# rpi2_ctrl.net
KiCad netlist of a schematic drawn in EAGLE
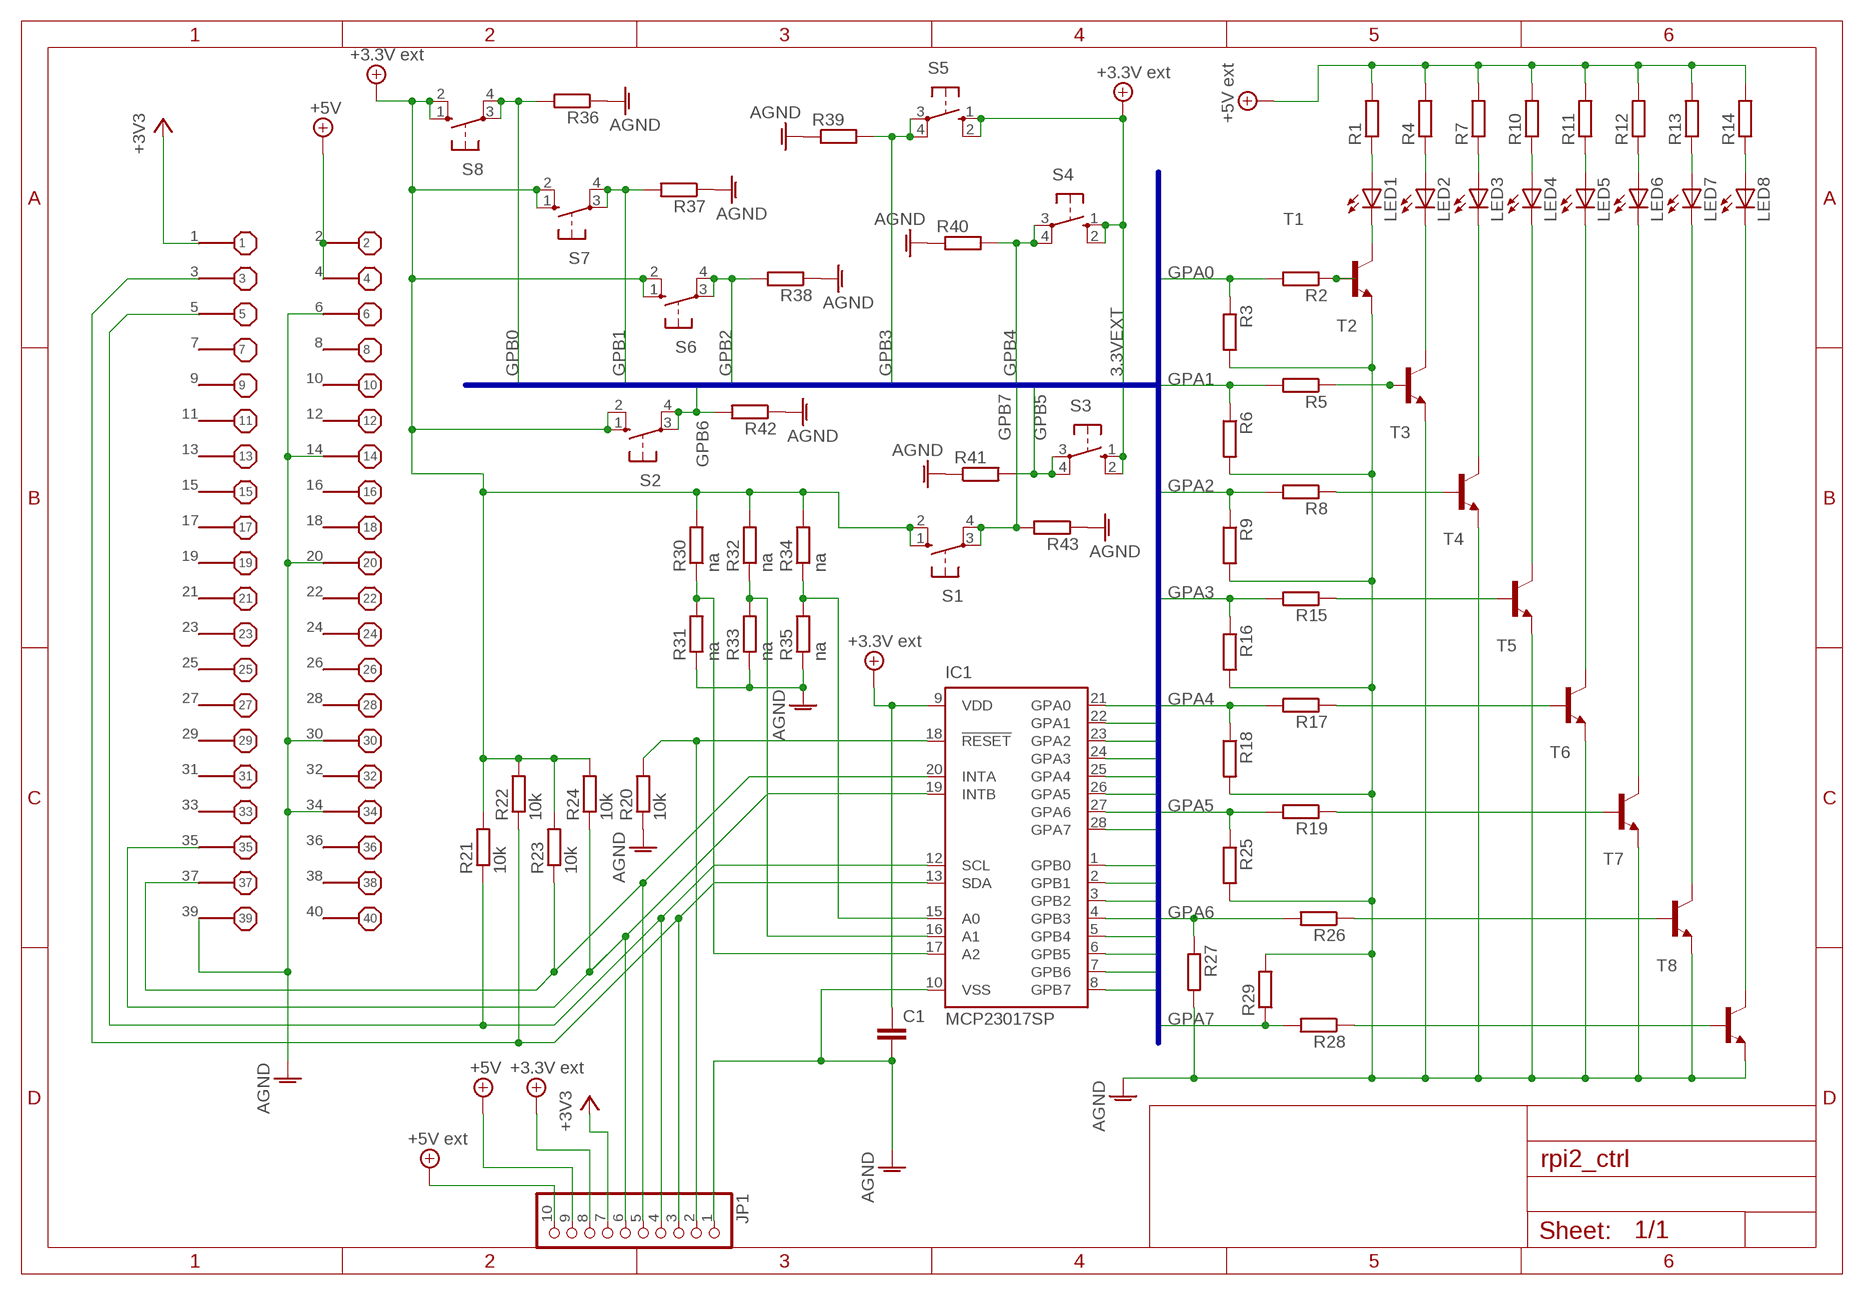
[diagram p0: schematic, sheet 1]

(export (version "E")
  (design (tool "Eeschema 10.0.6"))
  (components
    (comp (ref "C1")
      (value "C-EUC1210")
      (footprint "eagle-import:C1210")
      (libsource (lib "eagle-import") (part "C-EUC1210"))
    )
    (comp (ref "IC1")
      (value "MCP23017SP")
      (footprint "eagle-import:DIL28-3")
      (fields (field (name "MF") "MICROCHIP") (field (name "MPN") "MCP23017-E/SP"))
      (libsource (lib "eagle-import") (part "MCP23017SP"))
    )
    (comp (ref "JP1")
      (value "PINHD-1X10")
      (footprint "eagle-import:1X10")
      (libsource (lib "eagle-import") (part "PINHD-1X10"))
    )
    (comp (ref "LED1")
      (value "LED5MM")
      (footprint "eagle-import:LED5MM")
      (libsource (lib "eagle-import") (part "LED5MM"))
    )
    (comp (ref "LED2")
      (value "LED5MM")
      (footprint "eagle-import:LED5MM")
      (libsource (lib "eagle-import") (part "LED5MM"))
    )
    (comp (ref "LED3")
      (value "LED5MM")
      (footprint "eagle-import:LED5MM")
      (libsource (lib "eagle-import") (part "LED5MM"))
    )
    (comp (ref "LED4")
      (value "LED5MM")
      (footprint "eagle-import:LED5MM")
      (libsource (lib "eagle-import") (part "LED5MM"))
    )
    (comp (ref "LED5")
      (value "LED5MM")
      (footprint "eagle-import:LED5MM")
      (libsource (lib "eagle-import") (part "LED5MM"))
    )
    (comp (ref "LED6")
      (value "LED5MM")
      (footprint "eagle-import:LED5MM")
      (libsource (lib "eagle-import") (part "LED5MM"))
    )
    (comp (ref "LED7")
      (value "LED5MM")
      (footprint "eagle-import:LED5MM")
      (libsource (lib "eagle-import") (part "LED5MM"))
    )
    (comp (ref "LED8")
      (value "LED5MM")
      (footprint "eagle-import:LED5MM")
      (libsource (lib "eagle-import") (part "LED5MM"))
    )
    (comp (ref "R1")
      (value "R-EU_R0805")
      (footprint "eagle-import:R0805")
      (libsource (lib "eagle-import") (part "R-EU_R0805"))
    )
    (comp (ref "R2")
      (value "R-EU_R0805")
      (footprint "eagle-import:R0805")
      (libsource (lib "eagle-import") (part "R-EU_R0805"))
    )
    (comp (ref "R3")
      (value "R-EU_R0805")
      (footprint "eagle-import:R0805")
      (libsource (lib "eagle-import") (part "R-EU_R0805"))
    )
    (comp (ref "R4")
      (value "R-EU_R0805")
      (footprint "eagle-import:R0805")
      (libsource (lib "eagle-import") (part "R-EU_R0805"))
    )
    (comp (ref "R5")
      (value "R-EU_R0805")
      (footprint "eagle-import:R0805")
      (libsource (lib "eagle-import") (part "R-EU_R0805"))
    )
    (comp (ref "R6")
      (value "R-EU_R0805")
      (footprint "eagle-import:R0805")
      (libsource (lib "eagle-import") (part "R-EU_R0805"))
    )
    (comp (ref "R7")
      (value "R-EU_R0805")
      (footprint "eagle-import:R0805")
      (libsource (lib "eagle-import") (part "R-EU_R0805"))
    )
    (comp (ref "R8")
      (value "R-EU_R0805")
      (footprint "eagle-import:R0805")
      (libsource (lib "eagle-import") (part "R-EU_R0805"))
    )
    (comp (ref "R9")
      (value "R-EU_R0805")
      (footprint "eagle-import:R0805")
      (libsource (lib "eagle-import") (part "R-EU_R0805"))
    )
    (comp (ref "R10")
      (value "R-EU_R0805")
      (footprint "eagle-import:R0805")
      (libsource (lib "eagle-import") (part "R-EU_R0805"))
    )
    (comp (ref "R11")
      (value "R-EU_R0805")
      (footprint "eagle-import:R0805")
      (libsource (lib "eagle-import") (part "R-EU_R0805"))
    )
    (comp (ref "R12")
      (value "R-EU_R0805")
      (footprint "eagle-import:R0805")
      (libsource (lib "eagle-import") (part "R-EU_R0805"))
    )
    (comp (ref "R13")
      (value "R-EU_R0805")
      (footprint "eagle-import:R0805")
      (libsource (lib "eagle-import") (part "R-EU_R0805"))
    )
    (comp (ref "R14")
      (value "R-EU_R0805")
      (footprint "eagle-import:R0805")
      (libsource (lib "eagle-import") (part "R-EU_R0805"))
    )
    (comp (ref "R15")
      (value "R-EU_R0805")
      (footprint "eagle-import:R0805")
      (libsource (lib "eagle-import") (part "R-EU_R0805"))
    )
    (comp (ref "R16")
      (value "R-EU_R0805")
      (footprint "eagle-import:R0805")
      (libsource (lib "eagle-import") (part "R-EU_R0805"))
    )
    (comp (ref "R17")
      (value "R-EU_R0805")
      (footprint "eagle-import:R0805")
      (libsource (lib "eagle-import") (part "R-EU_R0805"))
    )
    (comp (ref "R18")
      (value "R-EU_R0805")
      (footprint "eagle-import:R0805")
      (libsource (lib "eagle-import") (part "R-EU_R0805"))
    )
    (comp (ref "R19")
      (value "R-EU_R0805")
      (footprint "eagle-import:R0805")
      (libsource (lib "eagle-import") (part "R-EU_R0805"))
    )
    (comp (ref "R20")
      (value "10k")
      (footprint "eagle-import:R0805")
      (libsource (lib "eagle-import") (part "R-EU_R0805"))
    )
    (comp (ref "R21")
      (value "10k")
      (footprint "eagle-import:R0805")
      (libsource (lib "eagle-import") (part "R-EU_R0805"))
    )
    (comp (ref "R22")
      (value "10k")
      (footprint "eagle-import:R0805")
      (libsource (lib "eagle-import") (part "R-EU_R0805"))
    )
    (comp (ref "R23")
      (value "10k")
      (footprint "eagle-import:R0805")
      (libsource (lib "eagle-import") (part "R-EU_R0805"))
    )
    (comp (ref "R24")
      (value "10k")
      (footprint "eagle-import:R0805")
      (libsource (lib "eagle-import") (part "R-EU_R0805"))
    )
    (comp (ref "R25")
      (value "R-EU_R0805")
      (footprint "eagle-import:R0805")
      (libsource (lib "eagle-import") (part "R-EU_R0805"))
    )
    (comp (ref "R26")
      (value "R-EU_R0805")
      (footprint "eagle-import:R0805")
      (libsource (lib "eagle-import") (part "R-EU_R0805"))
    )
    (comp (ref "R27")
      (value "R-EU_R0805")
      (footprint "eagle-import:R0805")
      (libsource (lib "eagle-import") (part "R-EU_R0805"))
    )
    (comp (ref "R28")
      (value "R-EU_R0805")
      (footprint "eagle-import:R0805")
      (libsource (lib "eagle-import") (part "R-EU_R0805"))
    )
    (comp (ref "R29")
      (value "R-EU_R0805")
      (footprint "eagle-import:R0805")
      (libsource (lib "eagle-import") (part "R-EU_R0805"))
    )
    (comp (ref "R30")
      (value "na")
      (footprint "eagle-import:R0805")
      (libsource (lib "eagle-import") (part "R-EU_R0805"))
    )
    (comp (ref "R31")
      (value "na")
      (footprint "eagle-import:R0805")
      (libsource (lib "eagle-import") (part "R-EU_R0805"))
    )
    (comp (ref "R32")
      (value "na")
      (footprint "eagle-import:R0805")
      (libsource (lib "eagle-import") (part "R-EU_R0805"))
    )
    (comp (ref "R33")
      (value "na")
      (footprint "eagle-import:R0805")
      (libsource (lib "eagle-import") (part "R-EU_R0805"))
    )
    (comp (ref "R34")
      (value "na")
      (footprint "eagle-import:R0805")
      (libsource (lib "eagle-import") (part "R-EU_R0805"))
    )
    (comp (ref "R35")
      (value "na")
      (footprint "eagle-import:R0805")
      (libsource (lib "eagle-import") (part "R-EU_R0805"))
    )
    (comp (ref "R36")
      (value "R-EU_R0805")
      (footprint "eagle-import:R0805")
      (libsource (lib "eagle-import") (part "R-EU_R0805"))
    )
    (comp (ref "R37")
      (value "R-EU_R0805")
      (footprint "eagle-import:R0805")
      (libsource (lib "eagle-import") (part "R-EU_R0805"))
    )
    (comp (ref "R38")
      (value "R-EU_R0805")
      (footprint "eagle-import:R0805")
      (libsource (lib "eagle-import") (part "R-EU_R0805"))
    )
    (comp (ref "R39")
      (value "R-EU_R0805")
      (footprint "eagle-import:R0805")
      (libsource (lib "eagle-import") (part "R-EU_R0805"))
    )
    (comp (ref "R40")
      (value "R-EU_R0805")
      (footprint "eagle-import:R0805")
      (libsource (lib "eagle-import") (part "R-EU_R0805"))
    )
    (comp (ref "R41")
      (value "R-EU_R0805")
      (footprint "eagle-import:R0805")
      (libsource (lib "eagle-import") (part "R-EU_R0805"))
    )
    (comp (ref "R42")
      (value "R-EU_R0805")
      (footprint "eagle-import:R0805")
      (libsource (lib "eagle-import") (part "R-EU_R0805"))
    )
    (comp (ref "R43")
      (value "R-EU_R0805")
      (footprint "eagle-import:R0805")
      (libsource (lib "eagle-import") (part "R-EU_R0805"))
    )
    (comp (ref "S1")
      (value "10-XX")
      (footprint "eagle-import:B3F-10XX")
      (fields (field (name "MPN") "B3F-1000"))
      (libsource (lib "eagle-import") (part "10-XX"))
    )
    (comp (ref "S2")
      (value "10-XX")
      (footprint "eagle-import:B3F-10XX")
      (fields (field (name "MPN") "B3F-1000"))
      (libsource (lib "eagle-import") (part "10-XX"))
    )
    (comp (ref "S3")
      (value "10-XX")
      (footprint "eagle-import:B3F-10XX")
      (fields (field (name "MPN") "B3F-1000"))
      (libsource (lib "eagle-import") (part "10-XX"))
    )
    (comp (ref "S4")
      (value "10-XX")
      (footprint "eagle-import:B3F-10XX")
      (fields (field (name "MPN") "B3F-1000"))
      (libsource (lib "eagle-import") (part "10-XX"))
    )
    (comp (ref "S5")
      (value "10-XX")
      (footprint "eagle-import:B3F-10XX")
      (fields (field (name "MPN") "B3F-1000"))
      (libsource (lib "eagle-import") (part "10-XX"))
    )
    (comp (ref "S6")
      (value "10-XX")
      (footprint "eagle-import:B3F-10XX")
      (fields (field (name "MPN") "B3F-1000"))
      (libsource (lib "eagle-import") (part "10-XX"))
    )
    (comp (ref "S7")
      (value "10-XX")
      (footprint "eagle-import:B3F-10XX")
      (fields (field (name "MPN") "B3F-1000"))
      (libsource (lib "eagle-import") (part "10-XX"))
    )
    (comp (ref "S8")
      (value "10-XX")
      (footprint "eagle-import:B3F-10XX")
      (fields (field (name "MPN") "B3F-1000"))
      (libsource (lib "eagle-import") (part "10-XX"))
    )
    (comp (ref "T1")
      (value "BC547-NPN-TO92-CBE")
      (footprint "eagle-import:TO92-CBE")
      (libsource (lib "eagle-import") (part "-NPN-TO92-CBEBC547"))
    )
    (comp (ref "T2")
      (value "BC547-NPN-TO92-CBE")
      (footprint "eagle-import:TO92-CBE")
      (libsource (lib "eagle-import") (part "-NPN-TO92-CBEBC547"))
    )
    (comp (ref "T3")
      (value "BC547-NPN-TO92-CBE")
      (footprint "eagle-import:TO92-CBE")
      (libsource (lib "eagle-import") (part "-NPN-TO92-CBEBC547"))
    )
    (comp (ref "T4")
      (value "BC547-NPN-TO92-CBE")
      (footprint "eagle-import:TO92-CBE")
      (libsource (lib "eagle-import") (part "-NPN-TO92-CBEBC547"))
    )
    (comp (ref "T5")
      (value "BC547-NPN-TO92-CBE")
      (footprint "eagle-import:TO92-CBE")
      (libsource (lib "eagle-import") (part "-NPN-TO92-CBEBC547"))
    )
    (comp (ref "T6")
      (value "BC547-NPN-TO92-CBE")
      (footprint "eagle-import:TO92-CBE")
      (libsource (lib "eagle-import") (part "-NPN-TO92-CBEBC547"))
    )
    (comp (ref "T7")
      (value "BC547-NPN-TO92-CBE")
      (footprint "eagle-import:TO92-CBE")
      (libsource (lib "eagle-import") (part "-NPN-TO92-CBEBC547"))
    )
    (comp (ref "T8")
      (value "BC547-NPN-TO92-CBE")
      (footprint "eagle-import:TO92-CBE")
      (libsource (lib "eagle-import") (part "-NPN-TO92-CBEBC547"))
    )
    (comp (ref "X1")
      (value "B+_GPIO")
      (footprint "eagle-import:B+_GPIO")
      (libsource (lib "eagle-import") (part "B+_GPIO"))
    )
  )
  (nets
    (net (code "1") (name "+3.3V ext") (class "Default")
      (node (ref "C1") (pin "1") (pinfunction "1_1") (pintype "passive"))
      (node (ref "IC1") (pin "9") (pinfunction "VDD_9") (pintype "power_in"))
      (node (ref "JP1") (pin "8") (pinfunction "8_8") (pintype "passive"))
      (node (ref "R21") (pin "2") (pinfunction "2_2") (pintype "passive"))
      (node (ref "R22") (pin "2") (pinfunction "2_2") (pintype "passive"))
      (node (ref "R23") (pin "2") (pinfunction "2_2") (pintype "passive"))
      (node (ref "R24") (pin "2") (pinfunction "2_2") (pintype "passive"))
      (node (ref "R30") (pin "2") (pinfunction "2_2") (pintype "passive"))
      (node (ref "R32") (pin "2") (pinfunction "2_2") (pintype "passive"))
      (node (ref "R34") (pin "2") (pinfunction "2_2") (pintype "passive"))
      (node (ref "S1") (pin "1") (pinfunction "S_1") (pintype "passive"))
      (node (ref "S1") (pin "2") (pinfunction "S1_2") (pintype "passive"))
      (node (ref "S2") (pin "1") (pinfunction "S_1") (pintype "passive"))
      (node (ref "S2") (pin "2") (pinfunction "S1_2") (pintype "passive"))
      (node (ref "S3") (pin "1") (pinfunction "S_1") (pintype "passive"))
      (node (ref "S3") (pin "2") (pinfunction "S1_2") (pintype "passive"))
      (node (ref "S4") (pin "1") (pinfunction "S_1") (pintype "passive"))
      (node (ref "S4") (pin "2") (pinfunction "S1_2") (pintype "passive"))
      (node (ref "S5") (pin "1") (pinfunction "S_1") (pintype "passive"))
      (node (ref "S5") (pin "2") (pinfunction "S1_2") (pintype "passive"))
      (node (ref "S6") (pin "1") (pinfunction "S_1") (pintype "passive"))
      (node (ref "S6") (pin "2") (pinfunction "S1_2") (pintype "passive"))
      (node (ref "S7") (pin "1") (pinfunction "S_1") (pintype "passive"))
      (node (ref "S7") (pin "2") (pinfunction "S1_2") (pintype "passive"))
      (node (ref "S8") (pin "1") (pinfunction "S_1") (pintype "passive"))
      (node (ref "S8") (pin "2") (pinfunction "S1_2") (pintype "passive"))
    )
    (net (code "2") (name "+3V3") (class "Default")
      (node (ref "JP1") (pin "7") (pinfunction "7_7") (pintype "passive"))
      (node (ref "X1") (pin "1") (pinfunction "P$1_1") (pintype "bidirectional"))
    )
    (net (code "3") (name "+5V") (class "Default")
      (node (ref "JP1") (pin "9") (pinfunction "9_9") (pintype "passive"))
      (node (ref "X1") (pin "2") (pinfunction "P$1_2") (pintype "bidirectional"))
      (node (ref "X1") (pin "4") (pinfunction "P$1_4") (pintype "bidirectional"))
    )
    (net (code "4") (name "+5V ext") (class "Default")
      (node (ref "JP1") (pin "10") (pinfunction "10_10") (pintype "passive"))
      (node (ref "R1") (pin "2") (pinfunction "2_2") (pintype "passive"))
      (node (ref "R10") (pin "2") (pinfunction "2_2") (pintype "passive"))
      (node (ref "R11") (pin "2") (pinfunction "2_2") (pintype "passive"))
      (node (ref "R12") (pin "2") (pinfunction "2_2") (pintype "passive"))
      (node (ref "R13") (pin "2") (pinfunction "2_2") (pintype "passive"))
      (node (ref "R14") (pin "2") (pinfunction "2_2") (pintype "passive"))
      (node (ref "R4") (pin "2") (pinfunction "2_2") (pintype "passive"))
      (node (ref "R7") (pin "2") (pinfunction "2_2") (pintype "passive"))
    )
    (net (code "5") (name "/GPA0") (class "Default")
      (node (ref "IC1") (pin "21") (pinfunction "GPA0_21") (pintype "bidirectional"))
      (node (ref "R2") (pin "2") (pinfunction "2_2") (pintype "passive"))
      (node (ref "R3") (pin "1") (pinfunction "1_1") (pintype "passive"))
    )
    (net (code "6") (name "/GPA1") (class "Default")
      (node (ref "IC1") (pin "22") (pinfunction "GPA1_22") (pintype "bidirectional"))
      (node (ref "R5") (pin "2") (pinfunction "2_2") (pintype "passive"))
      (node (ref "R6") (pin "1") (pinfunction "1_1") (pintype "passive"))
    )
    (net (code "7") (name "/GPA2") (class "Default")
      (node (ref "IC1") (pin "23") (pinfunction "GPA2_23") (pintype "bidirectional"))
      (node (ref "R8") (pin "2") (pinfunction "2_2") (pintype "passive"))
      (node (ref "R9") (pin "1") (pinfunction "1_1") (pintype "passive"))
    )
    (net (code "8") (name "/GPA3") (class "Default")
      (node (ref "IC1") (pin "24") (pinfunction "GPA3_24") (pintype "bidirectional"))
      (node (ref "R15") (pin "2") (pinfunction "2_2") (pintype "passive"))
      (node (ref "R16") (pin "1") (pinfunction "1_1") (pintype "passive"))
    )
    (net (code "9") (name "/GPA4") (class "Default")
      (node (ref "IC1") (pin "25") (pinfunction "GPA4_25") (pintype "bidirectional"))
      (node (ref "R17") (pin "2") (pinfunction "2_2") (pintype "passive"))
      (node (ref "R18") (pin "1") (pinfunction "1_1") (pintype "passive"))
    )
    (net (code "10") (name "/GPA5") (class "Default")
      (node (ref "IC1") (pin "26") (pinfunction "GPA5_26") (pintype "bidirectional"))
      (node (ref "R19") (pin "2") (pinfunction "2_2") (pintype "passive"))
      (node (ref "R25") (pin "1") (pinfunction "1_1") (pintype "passive"))
    )
    (net (code "11") (name "/GPA6") (class "Default")
      (node (ref "IC1") (pin "27") (pinfunction "GPA6_27") (pintype "bidirectional"))
      (node (ref "R26") (pin "2") (pinfunction "2_2") (pintype "passive"))
      (node (ref "R27") (pin "1") (pinfunction "1_1") (pintype "passive"))
    )
    (net (code "12") (name "/GPA7") (class "Default")
      (node (ref "IC1") (pin "28") (pinfunction "GPA7_28") (pintype "bidirectional"))
      (node (ref "R28") (pin "2") (pinfunction "2_2") (pintype "passive"))
      (node (ref "R29") (pin "1") (pinfunction "1_1") (pintype "passive"))
    )
    (net (code "13") (name "/GPB0") (class "Default")
      (node (ref "IC1") (pin "1") (pinfunction "GPB0_1") (pintype "bidirectional"))
      (node (ref "R36") (pin "2") (pinfunction "2_2") (pintype "passive"))
      (node (ref "S8") (pin "3") (pinfunction "P_3") (pintype "passive"))
      (node (ref "S8") (pin "4") (pinfunction "P1_4") (pintype "passive"))
    )
    (net (code "14") (name "/GPB1") (class "Default")
      (node (ref "IC1") (pin "2") (pinfunction "GPB1_2") (pintype "bidirectional"))
      (node (ref "R37") (pin "2") (pinfunction "2_2") (pintype "passive"))
      (node (ref "S7") (pin "3") (pinfunction "P_3") (pintype "passive"))
      (node (ref "S7") (pin "4") (pinfunction "P1_4") (pintype "passive"))
    )
    (net (code "15") (name "/GPB2") (class "Default")
      (node (ref "IC1") (pin "3") (pinfunction "GPB2_3") (pintype "bidirectional"))
      (node (ref "R38") (pin "2") (pinfunction "2_2") (pintype "passive"))
      (node (ref "S6") (pin "3") (pinfunction "P_3") (pintype "passive"))
      (node (ref "S6") (pin "4") (pinfunction "P1_4") (pintype "passive"))
    )
    (net (code "16") (name "/GPB3") (class "Default")
      (node (ref "IC1") (pin "4") (pinfunction "GPB3_4") (pintype "bidirectional"))
      (node (ref "R39") (pin "2") (pinfunction "2_2") (pintype "passive"))
      (node (ref "S5") (pin "3") (pinfunction "P_3") (pintype "passive"))
      (node (ref "S5") (pin "4") (pinfunction "P1_4") (pintype "passive"))
    )
    (net (code "17") (name "/GPB4") (class "Default")
      (node (ref "IC1") (pin "5") (pinfunction "GPB4_5") (pintype "bidirectional"))
      (node (ref "R40") (pin "2") (pinfunction "2_2") (pintype "passive"))
      (node (ref "S4") (pin "3") (pinfunction "P_3") (pintype "passive"))
      (node (ref "S4") (pin "4") (pinfunction "P1_4") (pintype "passive"))
    )
    (net (code "18") (name "/GPB5") (class "Default")
      (node (ref "IC1") (pin "6") (pinfunction "GPB5_6") (pintype "bidirectional"))
      (node (ref "R41") (pin "2") (pinfunction "2_2") (pintype "passive"))
      (node (ref "S3") (pin "3") (pinfunction "P_3") (pintype "passive"))
      (node (ref "S3") (pin "4") (pinfunction "P1_4") (pintype "passive"))
    )
    (net (code "19") (name "/GPB6") (class "Default")
      (node (ref "IC1") (pin "7") (pinfunction "GPB6_7") (pintype "bidirectional"))
      (node (ref "R42") (pin "2") (pinfunction "2_2") (pintype "passive"))
      (node (ref "S2") (pin "3") (pinfunction "P_3") (pintype "passive"))
      (node (ref "S2") (pin "4") (pinfunction "P1_4") (pintype "passive"))
    )
    (net (code "20") (name "/GPB7") (class "Default")
      (node (ref "IC1") (pin "8") (pinfunction "GPB7_8") (pintype "bidirectional"))
      (node (ref "R43") (pin "2") (pinfunction "2_2") (pintype "passive"))
      (node (ref "S1") (pin "3") (pinfunction "P_3") (pintype "passive"))
      (node (ref "S1") (pin "4") (pinfunction "P1_4") (pintype "passive"))
    )
    (net (code "21") (name "AGND") (class "Default")
      (node (ref "C1") (pin "2") (pinfunction "2_2") (pintype "passive"))
      (node (ref "IC1") (pin "10") (pinfunction "VSS_10") (pintype "power_in"))
      (node (ref "JP1") (pin "1") (pinfunction "1_1") (pintype "passive"))
      (node (ref "R16") (pin "2") (pinfunction "2_2") (pintype "passive"))
      (node (ref "R18") (pin "2") (pinfunction "2_2") (pintype "passive"))
      (node (ref "R20") (pin "1") (pinfunction "1_1") (pintype "passive"))
      (node (ref "R25") (pin "2") (pinfunction "2_2") (pintype "passive"))
      (node (ref "R27") (pin "2") (pinfunction "2_2") (pintype "passive"))
      (node (ref "R29") (pin "2") (pinfunction "2_2") (pintype "passive"))
      (node (ref "R3") (pin "2") (pinfunction "2_2") (pintype "passive"))
      (node (ref "R31") (pin "1") (pinfunction "1_1") (pintype "passive"))
      (node (ref "R33") (pin "1") (pinfunction "1_1") (pintype "passive"))
      (node (ref "R35") (pin "1") (pinfunction "1_1") (pintype "passive"))
      (node (ref "R36") (pin "1") (pinfunction "1_1") (pintype "passive"))
      (node (ref "R37") (pin "1") (pinfunction "1_1") (pintype "passive"))
      (node (ref "R38") (pin "1") (pinfunction "1_1") (pintype "passive"))
      (node (ref "R39") (pin "1") (pinfunction "1_1") (pintype "passive"))
      (node (ref "R40") (pin "1") (pinfunction "1_1") (pintype "passive"))
      (node (ref "R41") (pin "1") (pinfunction "1_1") (pintype "passive"))
      (node (ref "R42") (pin "1") (pinfunction "1_1") (pintype "passive"))
      (node (ref "R43") (pin "1") (pinfunction "1_1") (pintype "passive"))
      (node (ref "R6") (pin "2") (pinfunction "2_2") (pintype "passive"))
      (node (ref "R9") (pin "2") (pinfunction "2_2") (pintype "passive"))
      (node (ref "T1") (pin "E") (pinfunction "E_E") (pintype "passive"))
      (node (ref "T2") (pin "E") (pinfunction "E_E") (pintype "passive"))
      (node (ref "T3") (pin "E") (pinfunction "E_E") (pintype "passive"))
      (node (ref "T4") (pin "E") (pinfunction "E_E") (pintype "passive"))
      (node (ref "T5") (pin "E") (pinfunction "E_E") (pintype "passive"))
      (node (ref "T6") (pin "E") (pinfunction "E_E") (pintype "passive"))
      (node (ref "T7") (pin "E") (pinfunction "E_E") (pintype "passive"))
      (node (ref "T8") (pin "E") (pinfunction "E_E") (pintype "passive"))
      (node (ref "X1") (pin "14") (pinfunction "P$1_14") (pintype "bidirectional"))
      (node (ref "X1") (pin "20") (pinfunction "P$1_20") (pintype "bidirectional"))
      (node (ref "X1") (pin "30") (pinfunction "P$1_30") (pintype "bidirectional"))
      (node (ref "X1") (pin "34") (pinfunction "P$1_34") (pintype "bidirectional"))
      (node (ref "X1") (pin "39") (pinfunction "P$1_39") (pintype "bidirectional"))
      (node (ref "X1") (pin "6") (pinfunction "P$1_6") (pintype "bidirectional"))
    )
    (net (code "22") (name "Net-(IC1-A0)") (class "Default")
      (node (ref "IC1") (pin "15") (pinfunction "A0_15") (pintype "input"))
      (node (ref "R34") (pin "1") (pinfunction "1_1") (pintype "passive"))
      (node (ref "R35") (pin "2") (pinfunction "2_2") (pintype "passive"))
    )
    (net (code "23") (name "Net-(IC1-A1)") (class "Default")
      (node (ref "IC1") (pin "16") (pinfunction "A1_16") (pintype "input"))
      (node (ref "R32") (pin "1") (pinfunction "1_1") (pintype "passive"))
      (node (ref "R33") (pin "2") (pinfunction "2_2") (pintype "passive"))
    )
    (net (code "24") (name "Net-(IC1-A2)") (class "Default")
      (node (ref "IC1") (pin "17") (pinfunction "A2_17") (pintype "input"))
      (node (ref "R30") (pin "1") (pinfunction "1_1") (pintype "passive"))
      (node (ref "R31") (pin "2") (pinfunction "2_2") (pintype "passive"))
    )
    (net (code "25") (name "Net-(IC1-INTA)") (class "Default")
      (node (ref "IC1") (pin "20") (pinfunction "INTA_20") (pintype "output"))
      (node (ref "JP1") (pin "5") (pinfunction "5_5") (pintype "passive"))
      (node (ref "R23") (pin "1") (pinfunction "1_1") (pintype "passive"))
      (node (ref "X1") (pin "37") (pinfunction "P$1_37") (pintype "bidirectional"))
    )
    (net (code "26") (name "Net-(IC1-INTB)") (class "Default")
      (node (ref "IC1") (pin "19") (pinfunction "INTB_19") (pintype "output"))
      (node (ref "JP1") (pin "6") (pinfunction "6_6") (pintype "passive"))
      (node (ref "R24") (pin "1") (pinfunction "1_1") (pintype "passive"))
      (node (ref "X1") (pin "35") (pinfunction "P$1_35") (pintype "bidirectional"))
    )
    (net (code "27") (name "Net-(IC1-SCL)") (class "Default")
      (node (ref "IC1") (pin "12") (pinfunction "SCL_12") (pintype "input"))
      (node (ref "JP1") (pin "4") (pinfunction "4_4") (pintype "passive"))
      (node (ref "R21") (pin "1") (pinfunction "1_1") (pintype "passive"))
      (node (ref "X1") (pin "5") (pinfunction "P$1_5") (pintype "bidirectional"))
    )
    (net (code "28") (name "Net-(IC1-SDA)") (class "Default")
      (node (ref "IC1") (pin "13") (pinfunction "SDA_13") (pintype "bidirectional"))
      (node (ref "JP1") (pin "3") (pinfunction "3_3") (pintype "passive"))
      (node (ref "R22") (pin "1") (pinfunction "1_1") (pintype "passive"))
      (node (ref "X1") (pin "3") (pinfunction "P$1_3") (pintype "bidirectional"))
    )
    (net (code "29") (name "Net-(IC1-~{RESET})") (class "Default")
      (node (ref "IC1") (pin "18") (pinfunction "~{RESET}_18") (pintype "input"))
      (node (ref "JP1") (pin "2") (pinfunction "2_2") (pintype "passive"))
      (node (ref "R20") (pin "2") (pinfunction "2_2") (pintype "passive"))
    )
    (net (code "30") (name "Net-(LED1-C)") (class "Default")
      (node (ref "LED1") (pin "K") (pinfunction "C_K") (pintype "passive"))
      (node (ref "T1") (pin "C") (pinfunction "C_C") (pintype "passive"))
    )
    (net (code "31") (name "Net-(LED1-PadA)") (class "Default")
      (node (ref "LED1") (pin "A") (pinfunction "A_A") (pintype "passive"))
      (node (ref "R1") (pin "1") (pinfunction "1_1") (pintype "passive"))
    )
    (net (code "32") (name "Net-(LED2-C)") (class "Default")
      (node (ref "LED2") (pin "K") (pinfunction "C_K") (pintype "passive"))
      (node (ref "T2") (pin "C") (pinfunction "C_C") (pintype "passive"))
    )
    (net (code "33") (name "Net-(LED2-PadA)") (class "Default")
      (node (ref "LED2") (pin "A") (pinfunction "A_A") (pintype "passive"))
      (node (ref "R4") (pin "1") (pinfunction "1_1") (pintype "passive"))
    )
    (net (code "34") (name "Net-(LED3-C)") (class "Default")
      (node (ref "LED3") (pin "K") (pinfunction "C_K") (pintype "passive"))
      (node (ref "T3") (pin "C") (pinfunction "C_C") (pintype "passive"))
    )
    (net (code "35") (name "Net-(LED3-PadA)") (class "Default")
      (node (ref "LED3") (pin "A") (pinfunction "A_A") (pintype "passive"))
      (node (ref "R7") (pin "1") (pinfunction "1_1") (pintype "passive"))
    )
    (net (code "36") (name "Net-(LED4-C)") (class "Default")
      (node (ref "LED4") (pin "K") (pinfunction "C_K") (pintype "passive"))
      (node (ref "T4") (pin "C") (pinfunction "C_C") (pintype "passive"))
    )
    (net (code "37") (name "Net-(LED4-PadA)") (class "Default")
      (node (ref "LED4") (pin "A") (pinfunction "A_A") (pintype "passive"))
      (node (ref "R10") (pin "1") (pinfunction "1_1") (pintype "passive"))
    )
    (net (code "38") (name "Net-(LED5-C)") (class "Default")
      (node (ref "LED5") (pin "K") (pinfunction "C_K") (pintype "passive"))
      (node (ref "T5") (pin "C") (pinfunction "C_C") (pintype "passive"))
    )
    (net (code "39") (name "Net-(LED5-PadA)") (class "Default")
      (node (ref "LED5") (pin "A") (pinfunction "A_A") (pintype "passive"))
      (node (ref "R11") (pin "1") (pinfunction "1_1") (pintype "passive"))
    )
    (net (code "40") (name "Net-(LED6-C)") (class "Default")
      (node (ref "LED6") (pin "K") (pinfunction "C_K") (pintype "passive"))
      (node (ref "T6") (pin "C") (pinfunction "C_C") (pintype "passive"))
    )
    (net (code "41") (name "Net-(LED6-PadA)") (class "Default")
      (node (ref "LED6") (pin "A") (pinfunction "A_A") (pintype "passive"))
      (node (ref "R12") (pin "1") (pinfunction "1_1") (pintype "passive"))
    )
    (net (code "42") (name "Net-(LED7-C)") (class "Default")
      (node (ref "LED7") (pin "K") (pinfunction "C_K") (pintype "passive"))
      (node (ref "T7") (pin "C") (pinfunction "C_C") (pintype "passive"))
    )
    (net (code "43") (name "Net-(LED7-PadA)") (class "Default")
      (node (ref "LED7") (pin "A") (pinfunction "A_A") (pintype "passive"))
      (node (ref "R13") (pin "1") (pinfunction "1_1") (pintype "passive"))
    )
    (net (code "44") (name "Net-(LED8-C)") (class "Default")
      (node (ref "LED8") (pin "K") (pinfunction "C_K") (pintype "passive"))
      (node (ref "T8") (pin "C") (pinfunction "C_C") (pintype "passive"))
    )
    (net (code "45") (name "Net-(LED8-PadA)") (class "Default")
      (node (ref "LED8") (pin "A") (pinfunction "A_A") (pintype "passive"))
      (node (ref "R14") (pin "1") (pinfunction "1_1") (pintype "passive"))
    )
    (net (code "46") (name "Net-(R2-Pad1)") (class "Default")
      (node (ref "R2") (pin "1") (pinfunction "1_1") (pintype "passive"))
      (node (ref "T1") (pin "B") (pinfunction "B_B") (pintype "passive"))
    )
    (net (code "47") (name "Net-(R5-Pad1)") (class "Default")
      (node (ref "R5") (pin "1") (pinfunction "1_1") (pintype "passive"))
      (node (ref "T2") (pin "B") (pinfunction "B_B") (pintype "passive"))
    )
    (net (code "48") (name "Net-(R8-Pad1)") (class "Default")
      (node (ref "R8") (pin "1") (pinfunction "1_1") (pintype "passive"))
      (node (ref "T3") (pin "B") (pinfunction "B_B") (pintype "passive"))
    )
    (net (code "49") (name "Net-(R15-Pad1)") (class "Default")
      (node (ref "R15") (pin "1") (pinfunction "1_1") (pintype "passive"))
      (node (ref "T4") (pin "B") (pinfunction "B_B") (pintype "passive"))
    )
    (net (code "50") (name "Net-(R17-Pad1)") (class "Default")
      (node (ref "R17") (pin "1") (pinfunction "1_1") (pintype "passive"))
      (node (ref "T5") (pin "B") (pinfunction "B_B") (pintype "passive"))
    )
    (net (code "51") (name "Net-(R19-Pad1)") (class "Default")
      (node (ref "R19") (pin "1") (pinfunction "1_1") (pintype "passive"))
      (node (ref "T6") (pin "B") (pinfunction "B_B") (pintype "passive"))
    )
    (net (code "52") (name "Net-(R26-Pad1)") (class "Default")
      (node (ref "R26") (pin "1") (pinfunction "1_1") (pintype "passive"))
      (node (ref "T7") (pin "B") (pinfunction "B_B") (pintype "passive"))
    )
    (net (code "53") (name "Net-(R28-Pad1)") (class "Default")
      (node (ref "R28") (pin "1") (pinfunction "1_1") (pintype "passive"))
      (node (ref "T8") (pin "B") (pinfunction "B_B") (pintype "passive"))
    )
    (net (code "54") (name "unconnected-(X1AA-P$1-Pad33)") (class "Default")
      (node (ref "X1") (pin "33") (pinfunction "P$1_33") (pintype "bidirectional"))
    )
    (net (code "55") (name "unconnected-(X1AD-P$1-Pad36)") (class "Default")
      (node (ref "X1") (pin "36") (pinfunction "P$1_36") (pintype "bidirectional"))
    )
    (net (code "56") (name "unconnected-(X1AF-P$1-Pad38)") (class "Default")
      (node (ref "X1") (pin "38") (pinfunction "P$1_38") (pintype "bidirectional"))
    )
    (net (code "57") (name "unconnected-(X1AI-P$1-Pad40)") (class "Default")
      (node (ref "X1") (pin "40") (pinfunction "P$1_40") (pintype "bidirectional"))
    )
    (net (code "58") (name "unconnected-(X1AL-P$1-Pad7)") (class "Default")
      (node (ref "X1") (pin "7") (pinfunction "P$1_7") (pintype "bidirectional"))
    )
    (net (code "59") (name "unconnected-(X1AM-P$1-Pad8)") (class "Default")
      (node (ref "X1") (pin "8") (pinfunction "P$1_8") (pintype "bidirectional"))
    )
    (net (code "60") (name "unconnected-(X1AN-P$1-Pad9)") (class "Default")
      (node (ref "X1") (pin "9") (pinfunction "P$1_9") (pintype "bidirectional"))
    )
    (net (code "61") (name "unconnected-(X1B-P$1-Pad10)") (class "Default")
      (node (ref "X1") (pin "10") (pinfunction "P$1_10") (pintype "bidirectional"))
    )
    (net (code "62") (name "unconnected-(X1C-P$1-Pad11)") (class "Default")
      (node (ref "X1") (pin "11") (pinfunction "P$1_11") (pintype "bidirectional"))
    )
    (net (code "63") (name "unconnected-(X1D-P$1-Pad12)") (class "Default")
      (node (ref "X1") (pin "12") (pinfunction "P$1_12") (pintype "bidirectional"))
    )
    (net (code "64") (name "unconnected-(X1E-P$1-Pad13)") (class "Default")
      (node (ref "X1") (pin "13") (pinfunction "P$1_13") (pintype "bidirectional"))
    )
    (net (code "65") (name "unconnected-(X1G-P$1-Pad15)") (class "Default")
      (node (ref "X1") (pin "15") (pinfunction "P$1_15") (pintype "bidirectional"))
    )
    (net (code "66") (name "unconnected-(X1H-P$1-Pad16)") (class "Default")
      (node (ref "X1") (pin "16") (pinfunction "P$1_16") (pintype "bidirectional"))
    )
    (net (code "67") (name "unconnected-(X1I-P$1-Pad17)") (class "Default")
      (node (ref "X1") (pin "17") (pinfunction "P$1_17") (pintype "bidirectional"))
    )
    (net (code "68") (name "unconnected-(X1J-P$1-Pad18)") (class "Default")
      (node (ref "X1") (pin "18") (pinfunction "P$1_18") (pintype "bidirectional"))
    )
    (net (code "69") (name "unconnected-(X1K-P$1-Pad19)") (class "Default")
      (node (ref "X1") (pin "19") (pinfunction "P$1_19") (pintype "bidirectional"))
    )
    (net (code "70") (name "unconnected-(X1N-P$1-Pad21)") (class "Default")
      (node (ref "X1") (pin "21") (pinfunction "P$1_21") (pintype "bidirectional"))
    )
    (net (code "71") (name "unconnected-(X1O-P$1-Pad22)") (class "Default")
      (node (ref "X1") (pin "22") (pinfunction "P$1_22") (pintype "bidirectional"))
    )
    (net (code "72") (name "unconnected-(X1P-P$1-Pad23)") (class "Default")
      (node (ref "X1") (pin "23") (pinfunction "P$1_23") (pintype "bidirectional"))
    )
    (net (code "73") (name "unconnected-(X1Q-P$1-Pad24)") (class "Default")
      (node (ref "X1") (pin "24") (pinfunction "P$1_24") (pintype "bidirectional"))
    )
    (net (code "74") (name "unconnected-(X1R-P$1-Pad25)") (class "Default")
      (node (ref "X1") (pin "25") (pinfunction "P$1_25") (pintype "bidirectional"))
    )
    (net (code "75") (name "unconnected-(X1S-P$1-Pad26)") (class "Default")
      (node (ref "X1") (pin "26") (pinfunction "P$1_26") (pintype "bidirectional"))
    )
    (net (code "76") (name "unconnected-(X1T-P$1-Pad27)") (class "Default")
      (node (ref "X1") (pin "27") (pinfunction "P$1_27") (pintype "bidirectional"))
    )
    (net (code "77") (name "unconnected-(X1U-P$1-Pad28)") (class "Default")
      (node (ref "X1") (pin "28") (pinfunction "P$1_28") (pintype "bidirectional"))
    )
    (net (code "78") (name "unconnected-(X1V-P$1-Pad29)") (class "Default")
      (node (ref "X1") (pin "29") (pinfunction "P$1_29") (pintype "bidirectional"))
    )
    (net (code "79") (name "unconnected-(X1Y-P$1-Pad31)") (class "Default")
      (node (ref "X1") (pin "31") (pinfunction "P$1_31") (pintype "bidirectional"))
    )
    (net (code "80") (name "unconnected-(X1Z-P$1-Pad32)") (class "Default")
      (node (ref "X1") (pin "32") (pinfunction "P$1_32") (pintype "bidirectional"))
    )
  )
)
